# Power.net
KiCad netlist of a schematic drawn in Altium Designer
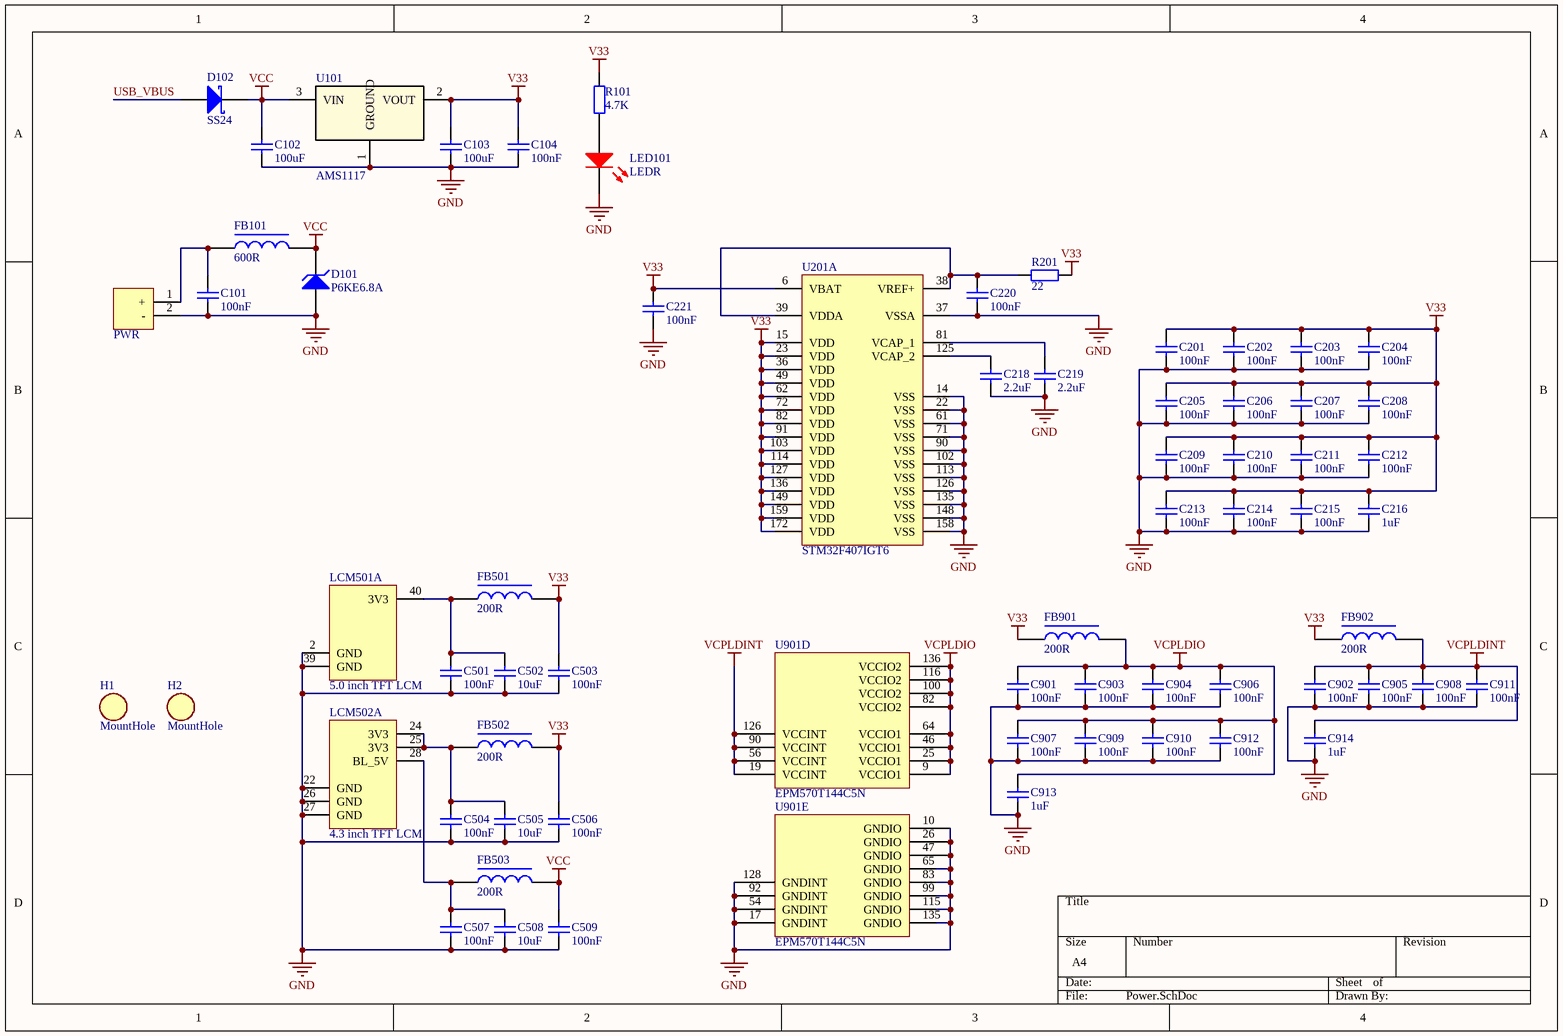
[diagram p0: Power.SchDoc]

(export (version "E")
  (design (tool "Eeschema 10.0.6"))
  (components
    (comp (ref "C101")
      (value "100nF")
      (footprint "0603C")
      (description "MLCC")
      (libsource (lib "Misc") (part "MLCC"))
    )
    (comp (ref "C102")
      (value "100uF")
      (footprint "1210C")
      (description "MLCC")
      (libsource (lib "Misc") (part "MLCC"))
    )
    (comp (ref "C103")
      (value "100uF")
      (footprint "1210C")
      (description "MLCC")
      (libsource (lib "Misc") (part "MLCC"))
    )
    (comp (ref "C104")
      (value "100nF")
      (footprint "0805C")
      (description "MLCC")
      (libsource (lib "Misc") (part "MLCC"))
    )
    (comp (ref "C201")
      (value "100nF")
      (footprint "0603C")
      (description "MLCC")
      (libsource (lib "Misc") (part "MLCC"))
    )
    (comp (ref "C202")
      (value "100nF")
      (footprint "0603C")
      (description "MLCC")
      (libsource (lib "Misc") (part "MLCC"))
    )
    (comp (ref "C203")
      (value "100nF")
      (footprint "0603C")
      (description "MLCC")
      (libsource (lib "Misc") (part "MLCC"))
    )
    (comp (ref "C204")
      (value "100nF")
      (footprint "0603C")
      (description "MLCC")
      (libsource (lib "Misc") (part "MLCC"))
    )
    (comp (ref "C205")
      (value "100nF")
      (footprint "0603C")
      (description "MLCC")
      (libsource (lib "Misc") (part "MLCC"))
    )
    (comp (ref "C206")
      (value "100nF")
      (footprint "0603C")
      (description "MLCC")
      (libsource (lib "Misc") (part "MLCC"))
    )
    (comp (ref "C207")
      (value "100nF")
      (footprint "0603C")
      (description "MLCC")
      (libsource (lib "Misc") (part "MLCC"))
    )
    (comp (ref "C208")
      (value "100nF")
      (footprint "0603C")
      (description "MLCC")
      (libsource (lib "Misc") (part "MLCC"))
    )
    (comp (ref "C209")
      (value "100nF")
      (footprint "0603C")
      (description "MLCC")
      (libsource (lib "Misc") (part "MLCC"))
    )
    (comp (ref "C210")
      (value "100nF")
      (footprint "0603C")
      (description "MLCC")
      (libsource (lib "Misc") (part "MLCC"))
    )
    (comp (ref "C211")
      (value "100nF")
      (footprint "0603C")
      (description "MLCC")
      (libsource (lib "Misc") (part "MLCC"))
    )
    (comp (ref "C212")
      (value "100nF")
      (footprint "0603C")
      (description "MLCC")
      (libsource (lib "Misc") (part "MLCC"))
    )
    (comp (ref "C213")
      (value "100nF")
      (footprint "0603C")
      (description "MLCC")
      (libsource (lib "Misc") (part "MLCC"))
    )
    (comp (ref "C214")
      (value "100nF")
      (footprint "0603C")
      (description "MLCC")
      (libsource (lib "Misc") (part "MLCC"))
    )
    (comp (ref "C215")
      (value "100nF")
      (footprint "0603C")
      (description "MLCC")
      (libsource (lib "Misc") (part "MLCC"))
    )
    (comp (ref "C216")
      (value "1uF")
      (footprint "0805C")
      (description "MLCC")
      (libsource (lib "Misc") (part "MLCC"))
    )
    (comp (ref "C218")
      (value "2.2uF")
      (footprint "0805C")
      (description "MLCC")
      (libsource (lib "Misc") (part "MLCC"))
    )
    (comp (ref "C219")
      (value "2.2uF")
      (footprint "0805C")
      (description "MLCC")
      (libsource (lib "Misc") (part "MLCC"))
    )
    (comp (ref "C220")
      (value "100nF")
      (footprint "0603C")
      (description "MLCC")
      (libsource (lib "Misc") (part "MLCC"))
    )
    (comp (ref "C221")
      (value "100nF")
      (footprint "0603C")
      (description "MLCC")
      (libsource (lib "Misc") (part "MLCC"))
    )
    (comp (ref "C501")
      (value "100nF")
      (footprint "0805C")
      (description "MLCC")
      (libsource (lib "Misc") (part "MLCC"))
    )
    (comp (ref "C502")
      (value "10uF")
      (footprint "0805C")
      (description "MLCC")
      (libsource (lib "Misc") (part "MLCC"))
    )
    (comp (ref "C503")
      (value "100nF")
      (footprint "0805C")
      (description "MLCC")
      (libsource (lib "Misc") (part "MLCC"))
    )
    (comp (ref "C504")
      (value "100nF")
      (footprint "0805C")
      (description "MLCC")
      (libsource (lib "Misc") (part "MLCC"))
    )
    (comp (ref "C505")
      (value "10uF")
      (footprint "0805C")
      (description "MLCC")
      (libsource (lib "Misc") (part "MLCC"))
    )
    (comp (ref "C506")
      (value "100nF")
      (footprint "0805C")
      (description "MLCC")
      (libsource (lib "Misc") (part "MLCC"))
    )
    (comp (ref "C507")
      (value "100nF")
      (footprint "0805C")
      (description "MLCC")
      (libsource (lib "Misc") (part "MLCC"))
    )
    (comp (ref "C508")
      (value "10uF")
      (footprint "0805C")
      (description "MLCC")
      (libsource (lib "Misc") (part "MLCC"))
    )
    (comp (ref "C509")
      (value "100nF")
      (footprint "0805C")
      (description "MLCC")
      (libsource (lib "Misc") (part "MLCC"))
    )
    (comp (ref "C901")
      (value "100nF")
      (footprint "0603C")
      (description "MLCC")
      (libsource (lib "Misc") (part "MLCC"))
    )
    (comp (ref "C902")
      (value "100nF")
      (footprint "0603C")
      (description "MLCC")
      (libsource (lib "Misc") (part "MLCC"))
    )
    (comp (ref "C903")
      (value "100nF")
      (footprint "0603C")
      (description "MLCC")
      (libsource (lib "Misc") (part "MLCC"))
    )
    (comp (ref "C904")
      (value "100nF")
      (footprint "0603C")
      (description "MLCC")
      (libsource (lib "Misc") (part "MLCC"))
    )
    (comp (ref "C905")
      (value "100nF")
      (footprint "0603C")
      (description "MLCC")
      (libsource (lib "Misc") (part "MLCC"))
    )
    (comp (ref "C906")
      (value "100nF")
      (footprint "0603C")
      (description "MLCC")
      (libsource (lib "Misc") (part "MLCC"))
    )
    (comp (ref "C907")
      (value "100nF")
      (footprint "0603C")
      (description "MLCC")
      (libsource (lib "Misc") (part "MLCC"))
    )
    (comp (ref "C908")
      (value "100nF")
      (footprint "0603C")
      (description "MLCC")
      (libsource (lib "Misc") (part "MLCC"))
    )
    (comp (ref "C909")
      (value "100nF")
      (footprint "0603C")
      (description "MLCC")
      (libsource (lib "Misc") (part "MLCC"))
    )
    (comp (ref "C910")
      (value "100nF")
      (footprint "0603C")
      (description "MLCC")
      (libsource (lib "Misc") (part "MLCC"))
    )
    (comp (ref "C911")
      (value "100nF")
      (footprint "0603C")
      (description "MLCC")
      (libsource (lib "Misc") (part "MLCC"))
    )
    (comp (ref "C912")
      (value "100nF")
      (footprint "0603C")
      (description "MLCC")
      (libsource (lib "Misc") (part "MLCC"))
    )
    (comp (ref "C913")
      (value "1uF")
      (footprint "0805C")
      (description "MLCC")
      (libsource (lib "Misc") (part "MLCC"))
    )
    (comp (ref "C914")
      (value "1uF")
      (footprint "0805C")
      (description "MLCC")
      (libsource (lib "Misc") (part "MLCC"))
    )
    (comp (ref "D101")
      (value "P6KE6.8A")
      (footprint "SMB")
      (description "600 Watt Peak Power Surmetict-40 Zener TransientVoltage Suppressors")
      (libsource (lib "Misc") (part "P6KE6.8A"))
    )
    (comp (ref "D102")
      (value "SS24")
      (footprint "SMA")
      (description "Schottky Rectifier")
      (libsource (lib "Misc") (part "SS24"))
    )
    (comp (ref "FB101")
      (value "600R")
      (footprint "1206L")
      (description "FerriteBead")
      (libsource (lib "Misc") (part "FerriteBead"))
    )
    (comp (ref "FB501")
      (value "200R")
      (footprint "0805L")
      (description "FerriteBead")
      (libsource (lib "Misc") (part "FerriteBead"))
    )
    (comp (ref "FB502")
      (value "200R")
      (footprint "0805L")
      (description "FerriteBead")
      (libsource (lib "Misc") (part "FerriteBead"))
    )
    (comp (ref "FB503")
      (value "200R")
      (footprint "0805L")
      (description "FerriteBead")
      (libsource (lib "Misc") (part "FerriteBead"))
    )
    (comp (ref "FB901")
      (value "200R")
      (footprint "0805L")
      (description "FerriteBead")
      (libsource (lib "Misc") (part "FerriteBead"))
    )
    (comp (ref "FB902")
      (value "200R")
      (footprint "0805L")
      (description "FerriteBead")
      (libsource (lib "Misc") (part "FerriteBead"))
    )
    (comp (ref "H1")
      (value "MountHole")
      (footprint "MOUNTHOLE")
      (description "3mm mount hole")
      (libsource (lib "Misc") (part "MountHole"))
    )
    (comp (ref "H2")
      (value "MountHole")
      (footprint "MOUNTHOLE")
      (description "3mm mount hole")
      (libsource (lib "Misc") (part "MountHole"))
    )
    (comp (ref "LCM501")
      (value "5.0 inch TFT LCM")
      (footprint "LCM5.0")
      (libsource (lib "LCM") (part "LCM5.0"))
    )
    (comp (ref "LCM502")
      (value "4.3 inch TFT LCM")
      (footprint "LCM4.3_ATK")
      (libsource (lib "LCM") (part "LCM4.3_ATK"))
    )
    (comp (ref "LED101")
      (value "LEDR")
      (footprint "LED1206R")
      (description "RED LED")
      (libsource (lib "Misc") (part "LEDR"))
    )
    (comp (ref "PWR")
      (value "WPORT2_PWR")
      (footprint "VH3.96-POWER-2P")
      (description "2 pin power port")
      (libsource (lib "Ports3.96") (part "WPORT2_PWR"))
    )
    (comp (ref "R101")
      (value "4.7K")
      (footprint "0603R")
      (description "Resistor")
      (libsource (lib "Misc") (part "Resistor"))
    )
    (comp (ref "R201")
      (value "22")
      (footprint "0603R")
      (description "Resistor")
      (libsource (lib "") (part "Resistor_1"))
    )
    (comp (ref "U101")
      (value "AMS1117")
      (footprint "DCY4")
      (description "800mA LOW DROPOUT VOLTAGE REGULATOR")
      (libsource (lib "LDO") (part "AMS1117"))
    )
    (comp (ref "U201")
      (value "STM32F407IGT6")
      (footprint "STM-LQFP176_N")
      (fields (field (name "MANUFACTURER") "STMicroelectronics"))
      (libsource (lib "STMicroelectronics STM32 F4") (part "STM32F407IGT6"))
    )
    (comp (ref "U901")
      (value "EPM570T144C5N")
      (footprint "TQFP144_N")
      (libsource (lib "Altera MAX II") (part "EPM570T144C5N"))
    )
  )
  (nets
    (net (code "1") (name "/USB_VBUS") (class "Default")
      (node (ref "D102") (pin "1") (pinfunction "A_1") (pintype "passive"))
    )
    (net (code "2") (name "GND") (class "Default")
      (node (ref "C101") (pin "1") (pinfunction "1_1") (pintype "passive"))
      (node (ref "C102") (pin "1") (pinfunction "1_1") (pintype "passive"))
      (node (ref "C103") (pin "1") (pinfunction "1_1") (pintype "passive"))
      (node (ref "C104") (pin "1") (pinfunction "1_1") (pintype "passive"))
      (node (ref "C201") (pin "1") (pinfunction "1_1") (pintype "passive"))
      (node (ref "C202") (pin "1") (pinfunction "1_1") (pintype "passive"))
      (node (ref "C203") (pin "1") (pinfunction "1_1") (pintype "passive"))
      (node (ref "C204") (pin "1") (pinfunction "1_1") (pintype "passive"))
      (node (ref "C205") (pin "1") (pinfunction "1_1") (pintype "passive"))
      (node (ref "C206") (pin "1") (pinfunction "1_1") (pintype "passive"))
      (node (ref "C207") (pin "1") (pinfunction "1_1") (pintype "passive"))
      (node (ref "C208") (pin "1") (pinfunction "1_1") (pintype "passive"))
      (node (ref "C209") (pin "1") (pinfunction "1_1") (pintype "passive"))
      (node (ref "C210") (pin "1") (pinfunction "1_1") (pintype "passive"))
      (node (ref "C211") (pin "1") (pinfunction "1_1") (pintype "passive"))
      (node (ref "C212") (pin "1") (pinfunction "1_1") (pintype "passive"))
      (node (ref "C213") (pin "1") (pinfunction "1_1") (pintype "passive"))
      (node (ref "C214") (pin "1") (pinfunction "1_1") (pintype "passive"))
      (node (ref "C215") (pin "1") (pinfunction "1_1") (pintype "passive"))
      (node (ref "C216") (pin "1") (pinfunction "1_1") (pintype "passive"))
      (node (ref "C218") (pin "1") (pinfunction "1_1") (pintype "passive"))
      (node (ref "C219") (pin "1") (pinfunction "1_1") (pintype "passive"))
      (node (ref "C220") (pin "1") (pinfunction "1_1") (pintype "passive"))
      (node (ref "C221") (pin "1") (pinfunction "1_1") (pintype "passive"))
      (node (ref "C501") (pin "1") (pinfunction "1_1") (pintype "passive"))
      (node (ref "C502") (pin "1") (pinfunction "1_1") (pintype "passive"))
      (node (ref "C503") (pin "1") (pinfunction "1_1") (pintype "passive"))
      (node (ref "C504") (pin "1") (pinfunction "1_1") (pintype "passive"))
      (node (ref "C505") (pin "1") (pinfunction "1_1") (pintype "passive"))
      (node (ref "C506") (pin "1") (pinfunction "1_1") (pintype "passive"))
      (node (ref "C507") (pin "1") (pinfunction "1_1") (pintype "passive"))
      (node (ref "C508") (pin "1") (pinfunction "1_1") (pintype "passive"))
      (node (ref "C509") (pin "1") (pinfunction "1_1") (pintype "passive"))
      (node (ref "C901") (pin "1") (pinfunction "1_1") (pintype "passive"))
      (node (ref "C902") (pin "1") (pinfunction "1_1") (pintype "passive"))
      (node (ref "C903") (pin "1") (pinfunction "1_1") (pintype "passive"))
      (node (ref "C904") (pin "1") (pinfunction "1_1") (pintype "passive"))
      (node (ref "C905") (pin "1") (pinfunction "1_1") (pintype "passive"))
      (node (ref "C906") (pin "1") (pinfunction "1_1") (pintype "passive"))
      (node (ref "C907") (pin "1") (pinfunction "1_1") (pintype "passive"))
      (node (ref "C908") (pin "1") (pinfunction "1_1") (pintype "passive"))
      (node (ref "C909") (pin "1") (pinfunction "1_1") (pintype "passive"))
      (node (ref "C910") (pin "1") (pinfunction "1_1") (pintype "passive"))
      (node (ref "C911") (pin "1") (pinfunction "1_1") (pintype "passive"))
      (node (ref "C912") (pin "1") (pinfunction "1_1") (pintype "passive"))
      (node (ref "C913") (pin "1") (pinfunction "1_1") (pintype "passive"))
      (node (ref "C914") (pin "1") (pinfunction "1_1") (pintype "passive"))
      (node (ref "D101") (pin "1") (pinfunction "A_1") (pintype "passive"))
      (node (ref "LCM501") (pin "2") (pinfunction "GND_2") (pintype "power_in"))
      (node (ref "LCM501") (pin "39") (pinfunction "GND_39") (pintype "power_in"))
      (node (ref "LCM502") (pin "22") (pinfunction "GND_22") (pintype "passive"))
      (node (ref "LCM502") (pin "26") (pinfunction "GND_26") (pintype "passive"))
      (node (ref "LCM502") (pin "27") (pinfunction "GND_27") (pintype "passive"))
      (node (ref "LED101") (pin "2") (pinfunction "K_2") (pintype "passive"))
      (node (ref "PWR") (pin "2") (pinfunction "-_2") (pintype "passive"))
      (node (ref "U101") (pin "1") (pinfunction "GROUND_1") (pintype "power_in"))
      (node (ref "U201") (pin "102") (pinfunction "VSS_102") (pintype "power_in"))
      (node (ref "U201") (pin "113") (pinfunction "VSS_113") (pintype "power_in"))
      (node (ref "U201") (pin "126") (pinfunction "VSS_126") (pintype "power_in"))
      (node (ref "U201") (pin "135") (pinfunction "VSS_135") (pintype "power_in"))
      (node (ref "U201") (pin "14") (pinfunction "VSS_14") (pintype "power_in"))
      (node (ref "U201") (pin "148") (pinfunction "VSS_148") (pintype "power_in"))
      (node (ref "U201") (pin "158") (pinfunction "VSS_158") (pintype "power_in"))
      (node (ref "U201") (pin "22") (pinfunction "VSS_22") (pintype "power_in"))
      (node (ref "U201") (pin "37") (pinfunction "VSSA_37") (pintype "power_in"))
      (node (ref "U201") (pin "61") (pinfunction "VSS_61") (pintype "power_in"))
      (node (ref "U201") (pin "71") (pinfunction "VSS_71") (pintype "power_in"))
      (node (ref "U201") (pin "90") (pinfunction "VSS_90") (pintype "power_in"))
      (node (ref "U901") (pin "10") (pinfunction "GNDIO_10") (pintype "power_in"))
      (node (ref "U901") (pin "115") (pinfunction "GNDIO_115") (pintype "power_in"))
      (node (ref "U901") (pin "128") (pinfunction "GNDINT_128") (pintype "power_in"))
      (node (ref "U901") (pin "135") (pinfunction "GNDIO_135") (pintype "power_in"))
      (node (ref "U901") (pin "17") (pinfunction "GNDINT_17") (pintype "power_in"))
      (node (ref "U901") (pin "26") (pinfunction "GNDIO_26") (pintype "power_in"))
      (node (ref "U901") (pin "47") (pinfunction "GNDIO_47") (pintype "power_in"))
      (node (ref "U901") (pin "54") (pinfunction "GNDINT_54") (pintype "power_in"))
      (node (ref "U901") (pin "65") (pinfunction "GNDIO_65") (pintype "power_in"))
      (node (ref "U901") (pin "83") (pinfunction "GNDIO_83") (pintype "power_in"))
      (node (ref "U901") (pin "92") (pinfunction "GNDINT_92") (pintype "power_in"))
      (node (ref "U901") (pin "99") (pinfunction "GNDIO_99") (pintype "power_in"))
    )
    (net (code "3") (name "Net-(C504-Pad2)") (class "Default")
      (node (ref "C504") (pin "2") (pinfunction "2_2") (pintype "passive"))
      (node (ref "C505") (pin "2") (pinfunction "2_2") (pintype "passive"))
      (node (ref "FB502") (pin "1") (pinfunction "1_1") (pintype "passive"))
      (node (ref "LCM502") (pin "24") (pinfunction "3V3_24") (pintype "passive"))
      (node (ref "LCM502") (pin "25") (pinfunction "3V3_25") (pintype "passive"))
    )
    (net (code "4") (name "Net-(LCM501A-3V3)") (class "Default")
      (node (ref "C501") (pin "2") (pinfunction "2_2") (pintype "passive"))
      (node (ref "C502") (pin "2") (pinfunction "2_2") (pintype "passive"))
      (node (ref "FB501") (pin "1") (pinfunction "1_1") (pintype "passive"))
      (node (ref "LCM501") (pin "40") (pinfunction "3V3_40") (pintype "power_in"))
    )
    (net (code "5") (name "Net-(LCM502A-BL_5V)") (class "Default")
      (node (ref "C507") (pin "2") (pinfunction "2_2") (pintype "passive"))
      (node (ref "C508") (pin "2") (pinfunction "2_2") (pintype "passive"))
      (node (ref "FB503") (pin "1") (pinfunction "1_1") (pintype "passive"))
      (node (ref "LCM502") (pin "28") (pinfunction "BL_5V_28") (pintype "passive"))
    )
    (net (code "6") (name "Net-(LED101-A)") (class "Default")
      (node (ref "LED101") (pin "1") (pinfunction "A_1") (pintype "passive"))
      (node (ref "R101") (pin "1") (pinfunction "1_1") (pintype "passive"))
    )
    (net (code "7") (name "Net-(PWR-+)") (class "Default")
      (node (ref "C101") (pin "2") (pinfunction "2_2") (pintype "passive"))
      (node (ref "FB101") (pin "1") (pinfunction "1_1") (pintype "passive"))
      (node (ref "PWR") (pin "1") (pinfunction "+_1") (pintype "passive"))
    )
    (net (code "8") (name "Net-(U201A-VCAP_1)") (class "Default")
      (node (ref "C219") (pin "2") (pinfunction "2_2") (pintype "passive"))
      (node (ref "U201") (pin "81") (pinfunction "VCAP_1_81") (pintype "power_in"))
    )
    (net (code "9") (name "Net-(U201A-VCAP_2)") (class "Default")
      (node (ref "C218") (pin "2") (pinfunction "2_2") (pintype "passive"))
      (node (ref "U201") (pin "125") (pinfunction "VCAP_2_125") (pintype "power_in"))
    )
    (net (code "10") (name "Net-(U201A-VDDA)") (class "Default")
      (node (ref "C220") (pin "2") (pinfunction "2_2") (pintype "passive"))
      (node (ref "R201") (pin "1") (pinfunction "1_1") (pintype "passive"))
      (node (ref "U201") (pin "38") (pinfunction "VREF+_38") (pintype "power_in"))
      (node (ref "U201") (pin "39") (pinfunction "VDDA_39") (pintype "power_in"))
    )
    (net (code "11") (name "V33") (class "Default")
      (node (ref "C103") (pin "2") (pinfunction "2_2") (pintype "passive"))
      (node (ref "C104") (pin "2") (pinfunction "2_2") (pintype "passive"))
      (node (ref "C201") (pin "2") (pinfunction "2_2") (pintype "passive"))
      (node (ref "C202") (pin "2") (pinfunction "2_2") (pintype "passive"))
      (node (ref "C203") (pin "2") (pinfunction "2_2") (pintype "passive"))
      (node (ref "C204") (pin "2") (pinfunction "2_2") (pintype "passive"))
      (node (ref "C205") (pin "2") (pinfunction "2_2") (pintype "passive"))
      (node (ref "C206") (pin "2") (pinfunction "2_2") (pintype "passive"))
      (node (ref "C207") (pin "2") (pinfunction "2_2") (pintype "passive"))
      (node (ref "C208") (pin "2") (pinfunction "2_2") (pintype "passive"))
      (node (ref "C209") (pin "2") (pinfunction "2_2") (pintype "passive"))
      (node (ref "C210") (pin "2") (pinfunction "2_2") (pintype "passive"))
      (node (ref "C211") (pin "2") (pinfunction "2_2") (pintype "passive"))
      (node (ref "C212") (pin "2") (pinfunction "2_2") (pintype "passive"))
      (node (ref "C213") (pin "2") (pinfunction "2_2") (pintype "passive"))
      (node (ref "C214") (pin "2") (pinfunction "2_2") (pintype "passive"))
      (node (ref "C215") (pin "2") (pinfunction "2_2") (pintype "passive"))
      (node (ref "C216") (pin "2") (pinfunction "2_2") (pintype "passive"))
      (node (ref "C221") (pin "2") (pinfunction "2_2") (pintype "passive"))
      (node (ref "C503") (pin "2") (pinfunction "2_2") (pintype "passive"))
      (node (ref "C506") (pin "2") (pinfunction "2_2") (pintype "passive"))
      (node (ref "FB501") (pin "2") (pinfunction "2_2") (pintype "passive"))
      (node (ref "FB502") (pin "2") (pinfunction "2_2") (pintype "passive"))
      (node (ref "FB901") (pin "1") (pinfunction "1_1") (pintype "passive"))
      (node (ref "FB902") (pin "1") (pinfunction "1_1") (pintype "passive"))
      (node (ref "R101") (pin "2") (pinfunction "2_2") (pintype "passive"))
      (node (ref "R201") (pin "2") (pinfunction "2_2") (pintype "passive"))
      (node (ref "U101") (pin "2") (pinfunction "VOUT_2") (pintype "power_in"))
      (node (ref "U201") (pin "103") (pinfunction "VDD_103") (pintype "power_in"))
      (node (ref "U201") (pin "114") (pinfunction "VDD_114") (pintype "power_in"))
      (node (ref "U201") (pin "127") (pinfunction "VDD_127") (pintype "power_in"))
      (node (ref "U201") (pin "136") (pinfunction "VDD_136") (pintype "power_in"))
      (node (ref "U201") (pin "149") (pinfunction "VDD_149") (pintype "power_in"))
      (node (ref "U201") (pin "15") (pinfunction "VDD_15") (pintype "power_in"))
      (node (ref "U201") (pin "159") (pinfunction "VDD_159") (pintype "power_in"))
      (node (ref "U201") (pin "172") (pinfunction "VDD_172") (pintype "power_in"))
      (node (ref "U201") (pin "23") (pinfunction "VDD_23") (pintype "power_in"))
      (node (ref "U201") (pin "36") (pinfunction "VDD_36") (pintype "power_in"))
      (node (ref "U201") (pin "49") (pinfunction "VDD_49") (pintype "power_in"))
      (node (ref "U201") (pin "6") (pinfunction "VBAT_6") (pintype "power_in"))
      (node (ref "U201") (pin "62") (pinfunction "VDD_62") (pintype "power_in"))
      (node (ref "U201") (pin "72") (pinfunction "VDD_72") (pintype "power_in"))
      (node (ref "U201") (pin "82") (pinfunction "VDD_82") (pintype "power_in"))
      (node (ref "U201") (pin "91") (pinfunction "VDD_91") (pintype "power_in"))
    )
    (net (code "12") (name "VCC") (class "Default")
      (node (ref "C102") (pin "2") (pinfunction "2_2") (pintype "passive"))
      (node (ref "C509") (pin "2") (pinfunction "2_2") (pintype "passive"))
      (node (ref "D101") (pin "2") (pinfunction "K_2") (pintype "passive"))
      (node (ref "D102") (pin "2") (pinfunction "K_2") (pintype "passive"))
      (node (ref "FB101") (pin "2") (pinfunction "2_2") (pintype "passive"))
      (node (ref "FB503") (pin "2") (pinfunction "2_2") (pintype "passive"))
      (node (ref "U101") (pin "3") (pinfunction "VIN_3") (pintype "power_in"))
    )
    (net (code "13") (name "VCPLDINT") (class "Default")
      (node (ref "C902") (pin "2") (pinfunction "2_2") (pintype "passive"))
      (node (ref "C905") (pin "2") (pinfunction "2_2") (pintype "passive"))
      (node (ref "C908") (pin "2") (pinfunction "2_2") (pintype "passive"))
      (node (ref "C911") (pin "2") (pinfunction "2_2") (pintype "passive"))
      (node (ref "C914") (pin "2") (pinfunction "2_2") (pintype "passive"))
      (node (ref "FB902") (pin "2") (pinfunction "2_2") (pintype "passive"))
      (node (ref "U901") (pin "126") (pinfunction "VCCINT_126") (pintype "power_in"))
      (node (ref "U901") (pin "19") (pinfunction "VCCINT_19") (pintype "power_in"))
      (node (ref "U901") (pin "56") (pinfunction "VCCINT_56") (pintype "power_in"))
      (node (ref "U901") (pin "90") (pinfunction "VCCINT_90") (pintype "power_in"))
    )
    (net (code "14") (name "VCPLDIO") (class "Default")
      (node (ref "C901") (pin "2") (pinfunction "2_2") (pintype "passive"))
      (node (ref "C903") (pin "2") (pinfunction "2_2") (pintype "passive"))
      (node (ref "C904") (pin "2") (pinfunction "2_2") (pintype "passive"))
      (node (ref "C906") (pin "2") (pinfunction "2_2") (pintype "passive"))
      (node (ref "C907") (pin "2") (pinfunction "2_2") (pintype "passive"))
      (node (ref "C909") (pin "2") (pinfunction "2_2") (pintype "passive"))
      (node (ref "C910") (pin "2") (pinfunction "2_2") (pintype "passive"))
      (node (ref "C912") (pin "2") (pinfunction "2_2") (pintype "passive"))
      (node (ref "C913") (pin "2") (pinfunction "2_2") (pintype "passive"))
      (node (ref "FB901") (pin "2") (pinfunction "2_2") (pintype "passive"))
      (node (ref "U901") (pin "100") (pinfunction "VCCIO2_100") (pintype "power_in"))
      (node (ref "U901") (pin "116") (pinfunction "VCCIO2_116") (pintype "power_in"))
      (node (ref "U901") (pin "136") (pinfunction "VCCIO2_136") (pintype "power_in"))
      (node (ref "U901") (pin "25") (pinfunction "VCCIO1_25") (pintype "power_in"))
      (node (ref "U901") (pin "46") (pinfunction "VCCIO1_46") (pintype "power_in"))
      (node (ref "U901") (pin "64") (pinfunction "VCCIO1_64") (pintype "power_in"))
      (node (ref "U901") (pin "82") (pinfunction "VCCIO2_82") (pintype "power_in"))
      (node (ref "U901") (pin "9") (pinfunction "VCCIO1_9") (pintype "power_in"))
    )
  )
)
